# tempShield.net
KiCad netlist of a schematic drawn in EAGLE
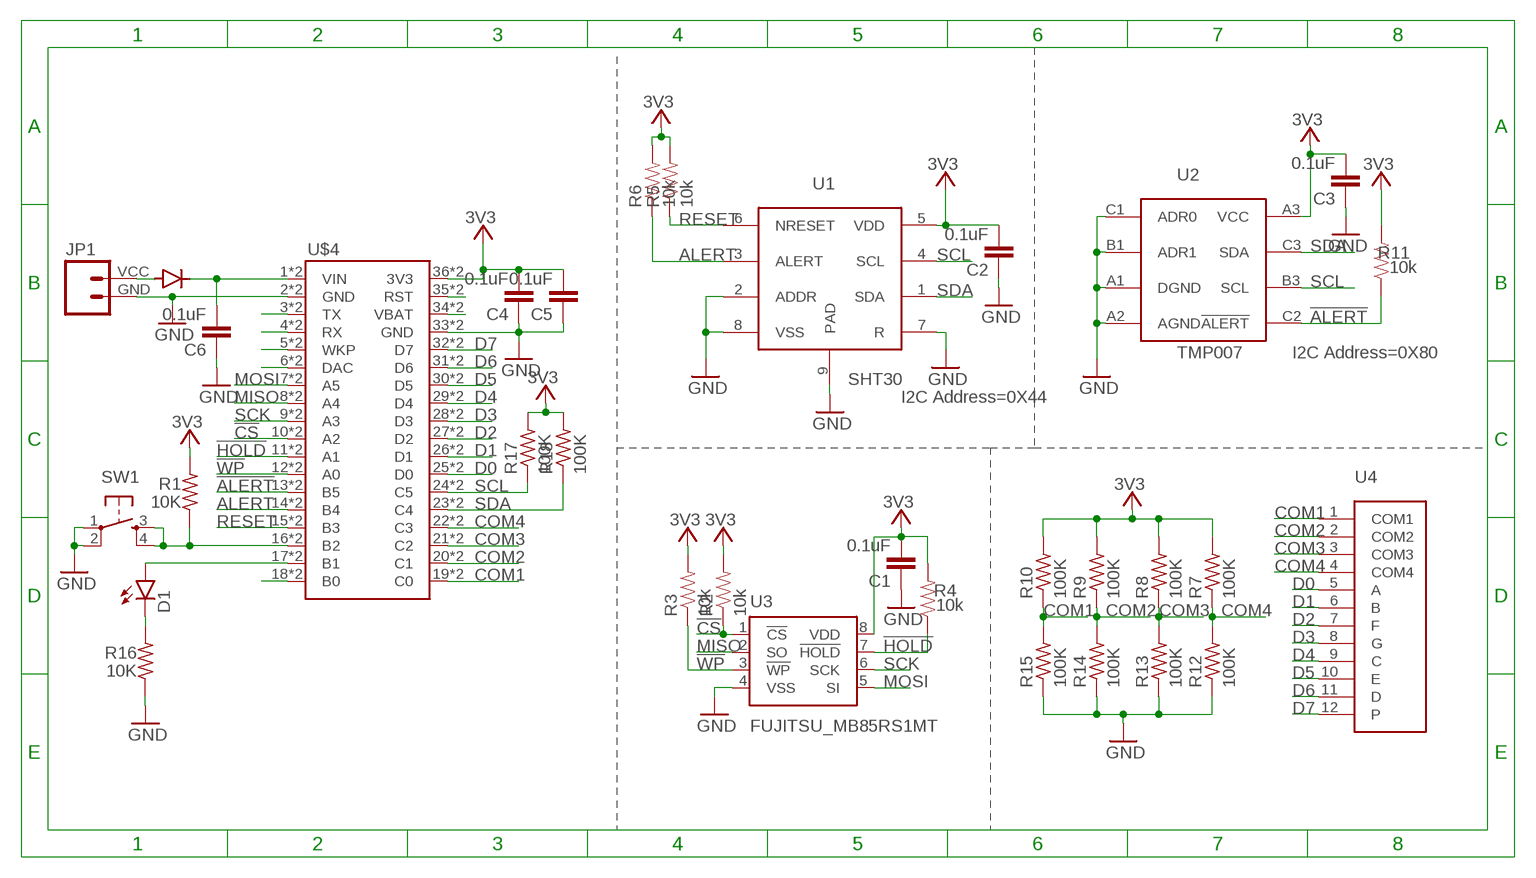
[diagram p0: schematic, sheet 1]

(export (version "E")
  (design (tool "Eeschema 10.0.6"))
  (components
    (comp (ref "C1")
      (value "0.1uF")
      (footprint "eagle-import:0603-CAP")
      (libsource (lib "eagle-import") (part "0.22UF50V-20%,+80%(0603)"))
    )
    (comp (ref "C2")
      (value "0.1uF")
      (footprint "eagle-import:0603-CAP")
      (libsource (lib "eagle-import") (part "0.22UF50V-20%,+80%(0603)"))
    )
    (comp (ref "C3")
      (value "0.1uF")
      (footprint "eagle-import:0603-CAP")
      (libsource (lib "eagle-import") (part "0.22UF50V-20%,+80%(0603)"))
    )
    (comp (ref "C4")
      (value "0.1uF")
      (footprint "eagle-import:0603-CAP")
      (libsource (lib "eagle-import") (part "0.22UF50V-20%,+80%(0603)"))
    )
    (comp (ref "C5")
      (value "0.1uF")
      (footprint "eagle-import:0603-CAP")
      (libsource (lib "eagle-import") (part "0.22UF50V-20%,+80%(0603)"))
    )
    (comp (ref "C6")
      (value "0.1uF")
      (footprint "eagle-import:0603-CAP")
      (libsource (lib "eagle-import") (part "0.22UF50V-20%,+80%(0603)"))
    )
    (comp (ref "D1")
      (value "LED0603")
      (footprint "eagle-import:LED-0603")
      (libsource (lib "eagle-import") (part "LED0603"))
    )
    (comp (ref "JP1")
      (value "SPARKFUN-CONNECTORS_M024UCON-15767")
      (footprint "eagle-import:SPARKFUN-CONNECTORS_JST-2-SMD-VERT")
      (libsource (lib "eagle-import") (part "SPARKFUN-CONNECTORS_M024UCON-15767"))
    )
    (comp (ref "R1")
      (value "10K")
      (footprint "eagle-import:R0402")
      (libsource (lib "eagle-import") (part "R-US_R0402"))
    )
    (comp (ref "R2")
      (value "10k")
      (footprint "eagle-import:0603-RES")
      (libsource (lib "eagle-import") (part "0.27OHM-1/10W-1%(0603)"))
    )
    (comp (ref "R3")
      (value "10k")
      (footprint "eagle-import:0603-RES")
      (libsource (lib "eagle-import") (part "0.27OHM-1/10W-1%(0603)"))
    )
    (comp (ref "R4")
      (value "10k")
      (footprint "eagle-import:0603-RES")
      (libsource (lib "eagle-import") (part "0.27OHM-1/10W-1%(0603)"))
    )
    (comp (ref "R5")
      (value "10k")
      (footprint "eagle-import:0603-RES")
      (libsource (lib "eagle-import") (part "0.27OHM-1/10W-1%(0603)"))
    )
    (comp (ref "R6")
      (value "10k")
      (footprint "eagle-import:0603-RES")
      (libsource (lib "eagle-import") (part "0.27OHM-1/10W-1%(0603)"))
    )
    (comp (ref "R7")
      (value "100K")
      (footprint "eagle-import:R0402")
      (libsource (lib "eagle-import") (part "R-US_R0402"))
    )
    (comp (ref "R8")
      (value "100K")
      (footprint "eagle-import:R0402")
      (libsource (lib "eagle-import") (part "R-US_R0402"))
    )
    (comp (ref "R9")
      (value "100K")
      (footprint "eagle-import:R0402")
      (libsource (lib "eagle-import") (part "R-US_R0402"))
    )
    (comp (ref "R10")
      (value "100K")
      (footprint "eagle-import:R0402")
      (libsource (lib "eagle-import") (part "R-US_R0402"))
    )
    (comp (ref "R11")
      (value "10k")
      (footprint "eagle-import:0603-RES")
      (libsource (lib "eagle-import") (part "0.27OHM-1/10W-1%(0603)"))
    )
    (comp (ref "R12")
      (value "100K")
      (footprint "eagle-import:R0402")
      (libsource (lib "eagle-import") (part "R-US_R0402"))
    )
    (comp (ref "R13")
      (value "100K")
      (footprint "eagle-import:R0402")
      (libsource (lib "eagle-import") (part "R-US_R0402"))
    )
    (comp (ref "R14")
      (value "100K")
      (footprint "eagle-import:R0402")
      (libsource (lib "eagle-import") (part "R-US_R0402"))
    )
    (comp (ref "R15")
      (value "100K")
      (footprint "eagle-import:R0402")
      (libsource (lib "eagle-import") (part "R-US_R0402"))
    )
    (comp (ref "R16")
      (value "10K")
      (footprint "eagle-import:R0402")
      (libsource (lib "eagle-import") (part "R-US_R0402"))
    )
    (comp (ref "R17")
      (value "100K")
      (footprint "eagle-import:R0402")
      (libsource (lib "eagle-import") (part "R-US_R0402"))
    )
    (comp (ref "R18")
      (value "100K")
      (footprint "eagle-import:R0402")
      (libsource (lib "eagle-import") (part "R-US_R0402"))
    )
    (comp (ref "SW1")
      (value "SWITCH_SPST_4_PIN")
      (footprint "eagle-import:TACTILE-SWITCH-SMD")
      (libsource (lib "eagle-import") (part "SWITCH_SPST_4_PIN"))
    )
    (comp (ref "U$1")
      (value "PARTICLE_DIODE_NT")
      (footprint "eagle-import:PARTICLE_DIODE-DO-220AA_NT(SMP)")
      (libsource (lib "eagle-import") (part "PARTICLE_DIODE_NT"))
    )
    (comp (ref "U$4")
      (value "MICROBUILDER_ELECTRON_SMT")
      (footprint "eagle-import:MICROBUILDER_ELECTRON_SMT")
      (libsource (lib "eagle-import") (part "MICROBUILDER_ELECTRON_SMT"))
    )
    (comp (ref "U1")
      (value "SHT30")
      (footprint "eagle-import:SHT30")
      (libsource (lib "eagle-import") (part "SHT30SHT30"))
    )
    (comp (ref "U2")
      (value "TMP007")
      (footprint "eagle-import:TMP007")
      (libsource (lib "eagle-import") (part "TMP007"))
    )
    (comp (ref "U3")
      (value "FUJITSU_MB85RS1MT")
      (footprint "eagle-import:FUJITSU_SO08")
      (libsource (lib "eagle-import") (part "FUJITSU_MB85RS1MT"))
    )
    (comp (ref "U4")
      (value "LCD")
      (footprint "eagle-import:LCD")
      (libsource (lib "eagle-import") (part "LCD"))
    )
  )
  (nets
    (net (code "1") (name "/ALERT") (class "Default")
      (node (ref "R6") (pin "1") (pinfunction "1_1") (pintype "passive"))
      (node (ref "U$4") (pin "14") (pinfunction "B4_14") (pintype "bidirectional"))
      (node (ref "U$4") (pin "14B") (pinfunction "B4_14B") (pintype "bidirectional"))
      (node (ref "U1") (pin "3") (pinfunction "ALERT_3") (pintype "bidirectional"))
    )
    (net (code "2") (name "/COM1") (class "Default")
      (node (ref "R10") (pin "1") (pinfunction "1_1") (pintype "passive"))
      (node (ref "R15") (pin "2") (pinfunction "2_2") (pintype "passive"))
      (node (ref "U$4") (pin "19") (pinfunction "C0_19") (pintype "bidirectional"))
      (node (ref "U$4") (pin "19B") (pinfunction "C0_19B") (pintype "bidirectional"))
      (node (ref "U4") (pin "1") (pinfunction "COM1_1") (pintype "bidirectional"))
    )
    (net (code "3") (name "/COM2") (class "Default")
      (node (ref "R14") (pin "2") (pinfunction "2_2") (pintype "passive"))
      (node (ref "R9") (pin "1") (pinfunction "1_1") (pintype "passive"))
      (node (ref "U$4") (pin "20") (pinfunction "C1_20") (pintype "bidirectional"))
      (node (ref "U$4") (pin "20B") (pinfunction "C1_20B") (pintype "bidirectional"))
      (node (ref "U4") (pin "2") (pinfunction "COM2_2") (pintype "bidirectional"))
    )
    (net (code "4") (name "/COM3") (class "Default")
      (node (ref "R13") (pin "2") (pinfunction "2_2") (pintype "passive"))
      (node (ref "R8") (pin "1") (pinfunction "1_1") (pintype "passive"))
      (node (ref "U$4") (pin "21") (pinfunction "C2_21") (pintype "bidirectional"))
      (node (ref "U$4") (pin "21B") (pinfunction "C2_21B") (pintype "bidirectional"))
      (node (ref "U4") (pin "3") (pinfunction "COM3_3") (pintype "bidirectional"))
    )
    (net (code "5") (name "/COM4") (class "Default")
      (node (ref "R12") (pin "2") (pinfunction "2_2") (pintype "passive"))
      (node (ref "R7") (pin "1") (pinfunction "1_1") (pintype "passive"))
      (node (ref "U$4") (pin "22") (pinfunction "C3_22") (pintype "bidirectional"))
      (node (ref "U$4") (pin "22B") (pinfunction "C3_22B") (pintype "bidirectional"))
      (node (ref "U4") (pin "4") (pinfunction "COM4_4") (pintype "bidirectional"))
    )
    (net (code "6") (name "/D0") (class "Default")
      (node (ref "U$4") (pin "25") (pinfunction "D0_25") (pintype "bidirectional"))
      (node (ref "U$4") (pin "25B") (pinfunction "D0_25B") (pintype "bidirectional"))
      (node (ref "U4") (pin "5") (pinfunction "A_5") (pintype "bidirectional"))
    )
    (net (code "7") (name "/D1") (class "Default")
      (node (ref "U$4") (pin "26") (pinfunction "D1_26") (pintype "bidirectional"))
      (node (ref "U$4") (pin "26B") (pinfunction "D1_26B") (pintype "bidirectional"))
      (node (ref "U4") (pin "6") (pinfunction "B_6") (pintype "bidirectional"))
    )
    (net (code "8") (name "/D2") (class "Default")
      (node (ref "U$4") (pin "27") (pinfunction "D2_27") (pintype "bidirectional"))
      (node (ref "U$4") (pin "27B") (pinfunction "D2_27B") (pintype "bidirectional"))
      (node (ref "U4") (pin "7") (pinfunction "F_7") (pintype "bidirectional"))
    )
    (net (code "9") (name "/D3") (class "Default")
      (node (ref "U$4") (pin "28") (pinfunction "D3_28") (pintype "bidirectional"))
      (node (ref "U$4") (pin "28B") (pinfunction "D3_28B") (pintype "bidirectional"))
      (node (ref "U4") (pin "8") (pinfunction "G_8") (pintype "bidirectional"))
    )
    (net (code "10") (name "/D4") (class "Default")
      (node (ref "U$4") (pin "29") (pinfunction "D4_29") (pintype "bidirectional"))
      (node (ref "U$4") (pin "29B") (pinfunction "D4_29B") (pintype "bidirectional"))
      (node (ref "U4") (pin "9") (pinfunction "C_9") (pintype "bidirectional"))
    )
    (net (code "11") (name "/D5") (class "Default")
      (node (ref "U$4") (pin "30") (pinfunction "D5_30") (pintype "bidirectional"))
      (node (ref "U$4") (pin "30B") (pinfunction "D5_30B") (pintype "bidirectional"))
      (node (ref "U4") (pin "10") (pinfunction "E_10") (pintype "bidirectional"))
    )
    (net (code "12") (name "/D6") (class "Default")
      (node (ref "U$4") (pin "31") (pinfunction "D6_31") (pintype "bidirectional"))
      (node (ref "U$4") (pin "31B") (pinfunction "D6_31B") (pintype "bidirectional"))
      (node (ref "U4") (pin "11") (pinfunction "D_11") (pintype "bidirectional"))
    )
    (net (code "13") (name "/D7") (class "Default")
      (node (ref "U$4") (pin "32") (pinfunction "D7_32") (pintype "bidirectional"))
      (node (ref "U$4") (pin "32B") (pinfunction "D7_32B") (pintype "bidirectional"))
      (node (ref "U4") (pin "12") (pinfunction "P_12") (pintype "bidirectional"))
    )
    (net (code "14") (name "/MISO") (class "Default")
      (node (ref "U$4") (pin "8") (pinfunction "A4_8") (pintype "bidirectional"))
      (node (ref "U$4") (pin "8B") (pinfunction "A4_8B") (pintype "bidirectional"))
      (node (ref "U3") (pin "2") (pinfunction "SO_2") (pintype "output"))
    )
    (net (code "15") (name "/MOSI") (class "Default")
      (node (ref "U$4") (pin "7") (pinfunction "A5_7") (pintype "bidirectional"))
      (node (ref "U$4") (pin "7B") (pinfunction "A5_7B") (pintype "bidirectional"))
      (node (ref "U3") (pin "5") (pinfunction "SI_5") (pintype "output"))
    )
    (net (code "16") (name "/RESET") (class "Default")
      (node (ref "R5") (pin "1") (pinfunction "1_1") (pintype "passive"))
      (node (ref "U$4") (pin "15") (pinfunction "B3_15") (pintype "bidirectional"))
      (node (ref "U$4") (pin "15B") (pinfunction "B3_15B") (pintype "bidirectional"))
      (node (ref "U1") (pin "6") (pinfunction "NRESET_6") (pintype "bidirectional"))
    )
    (net (code "17") (name "/SCK") (class "Default")
      (node (ref "U$4") (pin "9") (pinfunction "A3_9") (pintype "bidirectional"))
      (node (ref "U$4") (pin "9B") (pinfunction "A3_9B") (pintype "bidirectional"))
      (node (ref "U3") (pin "6") (pinfunction "SCK_6") (pintype "input"))
    )
    (net (code "18") (name "/SCL") (class "Default")
      (node (ref "R17") (pin "1") (pinfunction "1_1") (pintype "passive"))
      (node (ref "U$4") (pin "24") (pinfunction "C5_24") (pintype "bidirectional"))
      (node (ref "U$4") (pin "24B") (pinfunction "C5_24B") (pintype "bidirectional"))
      (node (ref "U1") (pin "4") (pinfunction "SCL_4") (pintype "bidirectional"))
      (node (ref "U2") (pin "B3") (pinfunction "SCL_B3") (pintype "bidirectional"))
    )
    (net (code "19") (name "/SDA") (class "Default")
      (node (ref "R18") (pin "1") (pinfunction "1_1") (pintype "passive"))
      (node (ref "U$4") (pin "23") (pinfunction "C4_23") (pintype "bidirectional"))
      (node (ref "U$4") (pin "23B") (pinfunction "C4_23B") (pintype "bidirectional"))
      (node (ref "U1") (pin "1") (pinfunction "SDA_1") (pintype "bidirectional"))
      (node (ref "U2") (pin "C3") (pinfunction "SDA_C3") (pintype "bidirectional"))
    )
    (net (code "20") (name "/~{ALERT}") (class "Default")
      (node (ref "R11") (pin "1") (pinfunction "1_1") (pintype "passive"))
      (node (ref "U$4") (pin "13") (pinfunction "B5_13") (pintype "bidirectional"))
      (node (ref "U$4") (pin "13B") (pinfunction "B5_13B") (pintype "bidirectional"))
      (node (ref "U2") (pin "C2") (pinfunction "~{ALERT}_C2") (pintype "bidirectional"))
    )
    (net (code "21") (name "/~{CS}") (class "Default")
      (node (ref "R2") (pin "1") (pinfunction "1_1") (pintype "passive"))
      (node (ref "U$4") (pin "10") (pinfunction "A2_10") (pintype "bidirectional"))
      (node (ref "U$4") (pin "10B") (pinfunction "A2_10B") (pintype "bidirectional"))
      (node (ref "U3") (pin "1") (pinfunction "~{CS}_1") (pintype "output"))
    )
    (net (code "22") (name "/~{HOLD}") (class "Default")
      (node (ref "R4") (pin "1") (pinfunction "1_1") (pintype "passive"))
      (node (ref "U$4") (pin "11") (pinfunction "A1_11") (pintype "bidirectional"))
      (node (ref "U$4") (pin "11B") (pinfunction "A1_11B") (pintype "bidirectional"))
      (node (ref "U3") (pin "7") (pinfunction "~{HOLD}_7") (pintype "output"))
    )
    (net (code "23") (name "/~{WP}") (class "Default")
      (node (ref "R3") (pin "1") (pinfunction "1_1") (pintype "passive"))
      (node (ref "U$4") (pin "12") (pinfunction "A0_12") (pintype "bidirectional"))
      (node (ref "U$4") (pin "12B") (pinfunction "A0_12B") (pintype "bidirectional"))
      (node (ref "U3") (pin "3") (pinfunction "~{WP}_3") (pintype "input"))
    )
    (net (code "24") (name "3V3") (class "Default")
      (node (ref "C1") (pin "2") (pinfunction "2_2") (pintype "passive"))
      (node (ref "C2") (pin "2") (pinfunction "2_2") (pintype "passive"))
      (node (ref "C3") (pin "2") (pinfunction "2_2") (pintype "passive"))
      (node (ref "C4") (pin "2") (pinfunction "2_2") (pintype "passive"))
      (node (ref "C5") (pin "2") (pinfunction "2_2") (pintype "passive"))
      (node (ref "R1") (pin "2") (pinfunction "2_2") (pintype "passive"))
      (node (ref "R10") (pin "2") (pinfunction "2_2") (pintype "passive"))
      (node (ref "R11") (pin "2") (pinfunction "2_2") (pintype "passive"))
      (node (ref "R17") (pin "2") (pinfunction "2_2") (pintype "passive"))
      (node (ref "R18") (pin "2") (pinfunction "2_2") (pintype "passive"))
      (node (ref "R2") (pin "2") (pinfunction "2_2") (pintype "passive"))
      (node (ref "R3") (pin "2") (pinfunction "2_2") (pintype "passive"))
      (node (ref "R4") (pin "2") (pinfunction "2_2") (pintype "passive"))
      (node (ref "R5") (pin "2") (pinfunction "2_2") (pintype "passive"))
      (node (ref "R6") (pin "2") (pinfunction "2_2") (pintype "passive"))
      (node (ref "R7") (pin "2") (pinfunction "2_2") (pintype "passive"))
      (node (ref "R8") (pin "2") (pinfunction "2_2") (pintype "passive"))
      (node (ref "R9") (pin "2") (pinfunction "2_2") (pintype "passive"))
      (node (ref "U$4") (pin "36") (pinfunction "3V3_36") (pintype "power_in"))
      (node (ref "U$4") (pin "36B") (pinfunction "3V3_36B") (pintype "power_in"))
      (node (ref "U1") (pin "5") (pinfunction "VDD_5") (pintype "bidirectional"))
      (node (ref "U2") (pin "A3") (pinfunction "VCC_A3") (pintype "bidirectional"))
      (node (ref "U3") (pin "8") (pinfunction "VDD_8") (pintype "power_in"))
    )
    (net (code "25") (name "GND") (class "Default")
      (node (ref "C1") (pin "1") (pinfunction "1_1") (pintype "passive"))
      (node (ref "C2") (pin "1") (pinfunction "1_1") (pintype "passive"))
      (node (ref "C3") (pin "1") (pinfunction "1_1") (pintype "passive"))
      (node (ref "C4") (pin "1") (pinfunction "1_1") (pintype "passive"))
      (node (ref "C5") (pin "1") (pinfunction "1_1") (pintype "passive"))
      (node (ref "C6") (pin "1") (pinfunction "1_1") (pintype "passive"))
      (node (ref "JP1") (pin "GND") (pinfunction "1_GND") (pintype "passive"))
      (node (ref "R12") (pin "1") (pinfunction "1_1") (pintype "passive"))
      (node (ref "R13") (pin "1") (pinfunction "1_1") (pintype "passive"))
      (node (ref "R14") (pin "1") (pinfunction "1_1") (pintype "passive"))
      (node (ref "R15") (pin "1") (pinfunction "1_1") (pintype "passive"))
      (node (ref "R16") (pin "1") (pinfunction "1_1") (pintype "passive"))
      (node (ref "SW1") (pin "1") (pinfunction "1_1") (pintype "passive"))
      (node (ref "SW1") (pin "2") (pinfunction "2_2") (pintype "passive"))
      (node (ref "U$4") (pin "2") (pinfunction "GND_2") (pintype "power_in"))
      (node (ref "U$4") (pin "2B") (pinfunction "GND_2B") (pintype "power_in"))
      (node (ref "U$4") (pin "33") (pinfunction "GND_33") (pintype "power_in"))
      (node (ref "U$4") (pin "33B") (pinfunction "GND_33B") (pintype "power_in"))
      (node (ref "U1") (pin "2") (pinfunction "ADDR_2") (pintype "bidirectional"))
      (node (ref "U1") (pin "7") (pinfunction "R_7") (pintype "bidirectional"))
      (node (ref "U1") (pin "8") (pinfunction "VSS_8") (pintype "bidirectional"))
      (node (ref "U1") (pin "9") (pinfunction "PAD_9") (pintype "bidirectional"))
      (node (ref "U2") (pin "A1") (pinfunction "DGND_A1") (pintype "bidirectional"))
      (node (ref "U2") (pin "A2") (pinfunction "AGND_A2") (pintype "bidirectional"))
      (node (ref "U2") (pin "B1") (pinfunction "ADR1_B1") (pintype "bidirectional"))
      (node (ref "U2") (pin "C1") (pinfunction "ADR0_C1") (pintype "bidirectional"))
      (node (ref "U3") (pin "4") (pinfunction "VSS_4") (pintype "power_in"))
    )
    (net (code "26") (name "Net-(C6-Pad2)") (class "Default")
      (node (ref "C6") (pin "2") (pinfunction "2_2") (pintype "passive"))
      (node (ref "U$1") (pin "CATHODE") (pinfunction "CATHODE_CATHODE") (pintype "bidirectional"))
      (node (ref "U$4") (pin "1") (pinfunction "VIN_1") (pintype "power_in"))
      (node (ref "U$4") (pin "1B") (pinfunction "VIN_1B") (pintype "power_in"))
    )
    (net (code "27") (name "Net-(D1-PadA)") (class "Default")
      (node (ref "D1") (pin "A") (pinfunction "A_A") (pintype "passive"))
      (node (ref "U$4") (pin "17") (pinfunction "B1_17") (pintype "bidirectional"))
      (node (ref "U$4") (pin "17B") (pinfunction "B1_17B") (pintype "bidirectional"))
    )
    (net (code "28") (name "Net-(D1-PadC)") (class "Default")
      (node (ref "D1") (pin "C") (pinfunction "C_C") (pintype "passive"))
      (node (ref "R16") (pin "2") (pinfunction "2_2") (pintype "passive"))
    )
    (net (code "29") (name "Net-(JP1-2)") (class "Default")
      (node (ref "JP1") (pin "VCC") (pinfunction "2_VCC") (pintype "passive"))
      (node (ref "U$1") (pin "ANODE") (pinfunction "ANODE_ANODE") (pintype "bidirectional"))
    )
    (net (code "30") (name "Net-(R1-Pad1)") (class "Default")
      (node (ref "R1") (pin "1") (pinfunction "1_1") (pintype "passive"))
      (node (ref "SW1") (pin "3") (pinfunction "3_3") (pintype "passive"))
      (node (ref "SW1") (pin "4") (pinfunction "4_4") (pintype "passive"))
      (node (ref "U$4") (pin "16") (pinfunction "B2_16") (pintype "bidirectional"))
      (node (ref "U$4") (pin "16B") (pinfunction "B2_16B") (pintype "bidirectional"))
    )
    (net (code "31") (name "Net-(U$4-B0-Pad18)") (class "Default")
      (node (ref "U$4") (pin "18") (pinfunction "B0_18") (pintype "bidirectional"))
      (node (ref "U$4") (pin "18B") (pinfunction "B0_18B") (pintype "bidirectional"))
    )
    (net (code "32") (name "Net-(U$4-DAC-Pad6)") (class "Default")
      (node (ref "U$4") (pin "6") (pinfunction "DAC_6") (pintype "bidirectional"))
      (node (ref "U$4") (pin "6B") (pinfunction "DAC_6B") (pintype "bidirectional"))
    )
    (net (code "33") (name "Net-(U$4-RST-Pad35)") (class "Default")
      (node (ref "U$4") (pin "35") (pinfunction "RST_35") (pintype "bidirectional"))
      (node (ref "U$4") (pin "35B") (pinfunction "RST_35B") (pintype "bidirectional"))
    )
    (net (code "34") (name "Net-(U$4-RX-Pad4)") (class "Default")
      (node (ref "U$4") (pin "4") (pinfunction "RX_4") (pintype "bidirectional"))
      (node (ref "U$4") (pin "4B") (pinfunction "RX_4B") (pintype "bidirectional"))
    )
    (net (code "35") (name "Net-(U$4-TX-Pad3)") (class "Default")
      (node (ref "U$4") (pin "3") (pinfunction "TX_3") (pintype "bidirectional"))
      (node (ref "U$4") (pin "3B") (pinfunction "TX_3B") (pintype "bidirectional"))
    )
    (net (code "36") (name "Net-(U$4-VBAT-Pad34)") (class "Default")
      (node (ref "U$4") (pin "34") (pinfunction "VBAT_34") (pintype "passive"))
      (node (ref "U$4") (pin "34B") (pinfunction "VBAT_34B") (pintype "passive"))
    )
    (net (code "37") (name "Net-(U$4-WKP-Pad5)") (class "Default")
      (node (ref "U$4") (pin "5") (pinfunction "WKP_5") (pintype "bidirectional"))
      (node (ref "U$4") (pin "5B") (pinfunction "WKP_5B") (pintype "bidirectional"))
    )
  )
)
